# Accelerometer.net
KiCad netlist of a schematic drawn in Altium Designer
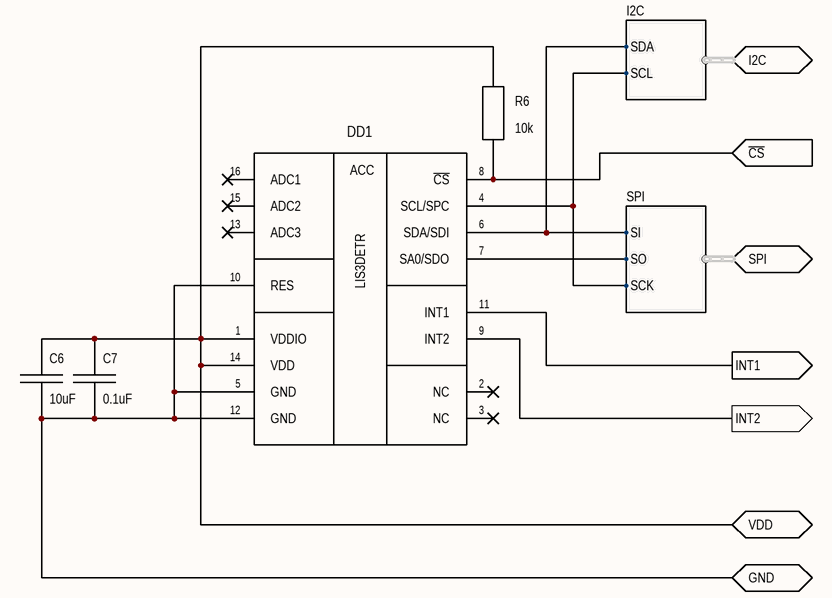
[diagram p0: Accelerometer.SchDoc]

(export (version "E")
  (design (tool "Eeschema 10.0.6"))
  (components
    (comp (ref "C6")
      (value "10uF")
      (footprint "CAPC2012L")
      (description "Capacitor Ceramic 10uF 25V")
      (fields (field (name "TOLERANCE") "±10%") (field (name "MANUFACTURER") "Yageo"))
      (libsource (lib "Capacitors") (part "CC0805KKX5R8BB106"))
    )
    (comp (ref "C7")
      (value "0.1uF")
      (footprint "CAPC1608L")
      (description "Capacitor Ceramic 0.1uF 25V")
      (fields (field (name "TOLERANCE") "±10%") (field (name "MANUFACTURER") "Yageo"))
      (libsource (lib "Capacitors") (part "CC0603KRX7R8BB104"))
    )
    (comp (ref "DD1")
      (value "LIS3DETR")
      (footprint "LGA-16")
      (description "MEMS Accelerometer")
      (fields (field (name "MANUFACTURER") "STMicroelectronics"))
      (libsource (lib "ICs") (part "LIS3DETR"))
    )
    (comp (ref "R6")
      (value "10k")
      (footprint "RESC1608L")
      (description "Resistor Ceramic 10k 1608")
      (fields (field (name "MANUFACTURER") "Yageo") (field (name "TOLERANCE") "±5%"))
      (libsource (lib "Resistors") (part "RC0603JR-0710KL"))
    )
  )
  (nets
    (net (code "3") (name "/GND") (class "Default")
      (node (ref "C6") (pin "2") (pinfunction "2_2") (pintype "passive"))
      (node (ref "C7") (pin "2") (pinfunction "2_2") (pintype "passive"))
      (node (ref "DD1") (pin "10") (pinfunction "RES_10") (pintype "passive"))
      (node (ref "DD1") (pin "12") (pinfunction "GND_12") (pintype "passive"))
      (node (ref "DD1") (pin "5") (pinfunction "GND_5") (pintype "passive"))
    )
    (net (code "4") (name "/INT1") (class "Default")
      (node (ref "DD1") (pin "11") (pinfunction "INT1_11") (pintype "passive"))
    )
    (net (code "5") (name "/INT2") (class "Default")
      (node (ref "DD1") (pin "9") (pinfunction "INT2_9") (pintype "passive"))
    )
    (net (code "6") (name "/SCK") (class "Default")
      (node (ref "DD1") (pin "4") (pinfunction "SCL/SPC_4") (pintype "passive"))
    )
    (net (code "7") (name "/SDA") (class "Default")
      (node (ref "DD1") (pin "6") (pinfunction "SDA/SDI_6") (pintype "passive"))
    )
    (net (code "8") (name "/SO") (class "Default")
      (node (ref "DD1") (pin "7") (pinfunction "SA0/SDO_7") (pintype "passive"))
    )
    (net (code "9") (name "/VDD") (class "Default")
      (node (ref "C6") (pin "1") (pinfunction "1_1") (pintype "passive"))
      (node (ref "C7") (pin "1") (pinfunction "1_1") (pintype "passive"))
      (node (ref "DD1") (pin "1") (pinfunction "VDDIO_1") (pintype "passive"))
      (node (ref "DD1") (pin "14") (pinfunction "VDD_14") (pintype "passive"))
      (node (ref "R6") (pin "1") (pinfunction "1_1") (pintype "passive"))
    )
    (net (code "12") (name "/~{CS}") (class "Default")
      (node (ref "DD1") (pin "8") (pinfunction "~{CS}_8") (pintype "passive"))
      (node (ref "R6") (pin "2") (pinfunction "2_2") (pintype "passive"))
    )
    (net (code "13") (name "unconnected-(DD1-ADC1-Pad16)") (class "Default")
      (node (ref "DD1") (pin "16") (pinfunction "ADC1_16") (pintype "passive+no_connect"))
    )
    (net (code "14") (name "unconnected-(DD1-ADC2-Pad15)") (class "Default")
      (node (ref "DD1") (pin "15") (pinfunction "ADC2_15") (pintype "passive+no_connect"))
    )
    (net (code "15") (name "unconnected-(DD1-ADC3-Pad13)") (class "Default")
      (node (ref "DD1") (pin "13") (pinfunction "ADC3_13") (pintype "passive+no_connect"))
    )
    (net (code "16") (name "unconnected-(DD1-NC-Pad2)") (class "Default")
      (node (ref "DD1") (pin "2") (pinfunction "NC_2") (pintype "passive+no_connect"))
    )
    (net (code "17") (name "unconnected-(DD1-NC-Pad3)") (class "Default")
      (node (ref "DD1") (pin "3") (pinfunction "NC_3") (pintype "passive+no_connect"))
    )
  )
)
